# CH32V002F4U6.net
KiCad netlist of a schematic drawn in Altium Designer
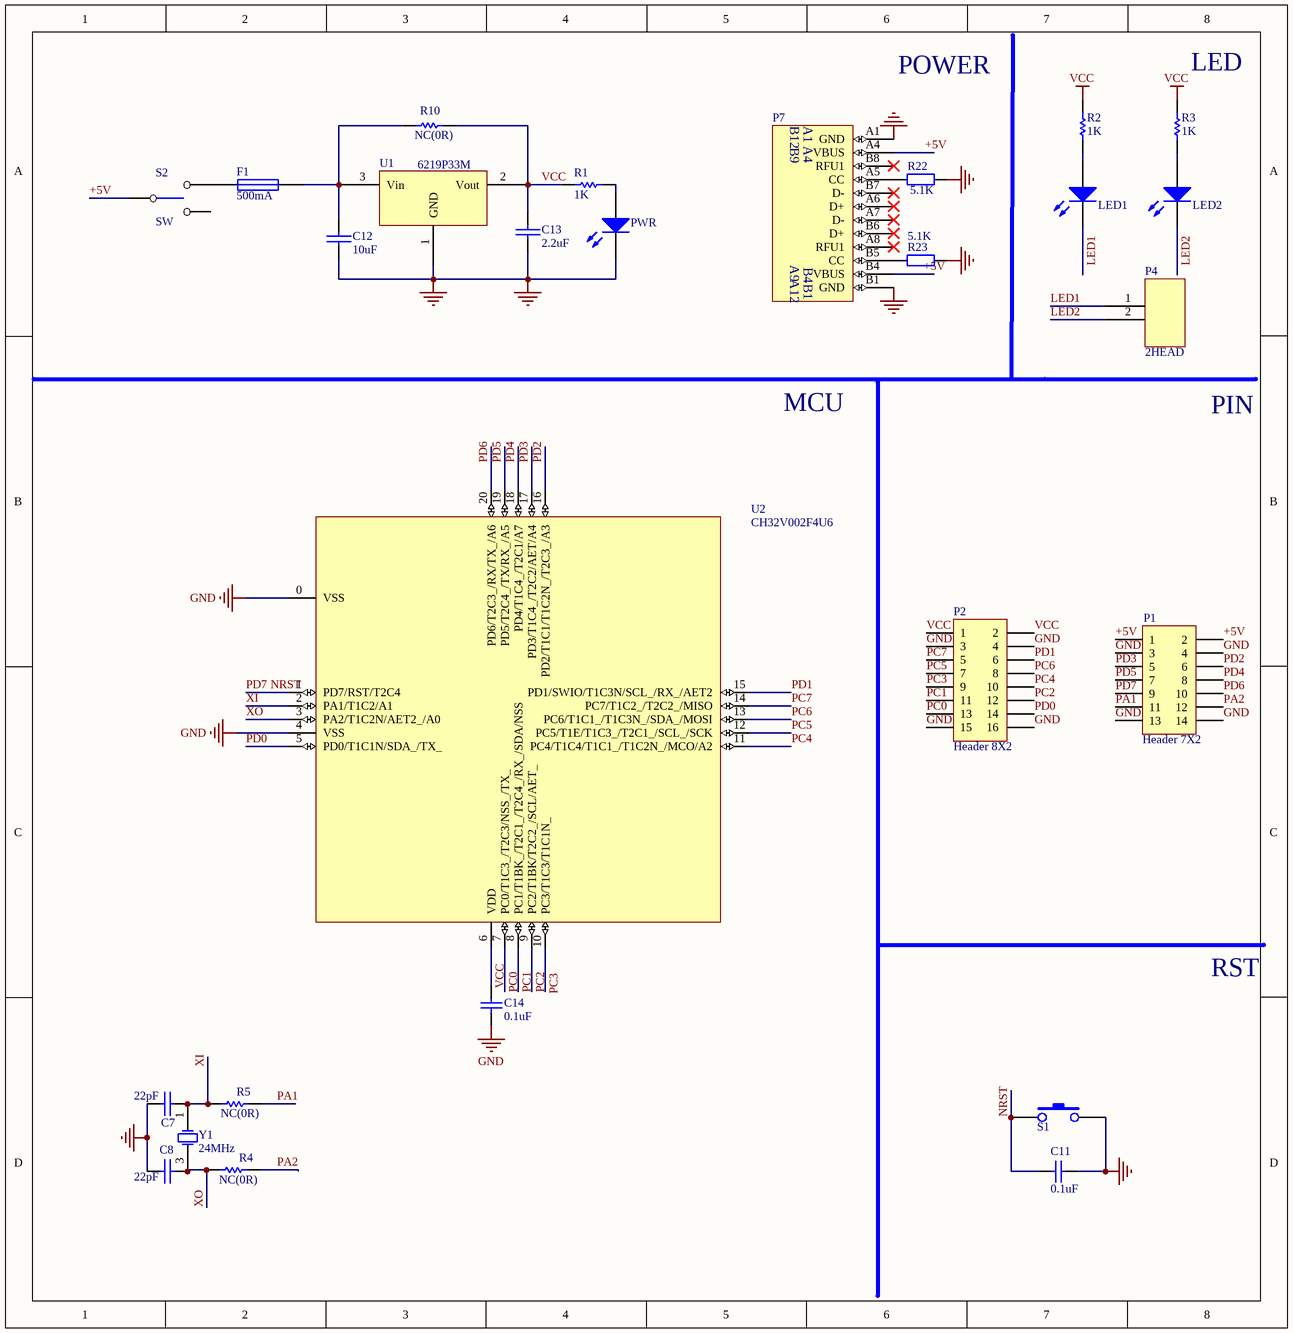
[diagram p0: CH32V002F4U6.SchDoc]

(export (version "E")
  (design (tool "Eeschema 10.0.6"))
  (components
    (comp (ref "C7")
      (value "22pF")
      (footprint "0402_C")
      (description "Capacitor")
      (libsource (lib "*") (part "CAP"))
    )
    (comp (ref "C8")
      (value "22pF")
      (footprint "0402_C")
      (description "Capacitor")
      (libsource (lib "*") (part "CAP"))
    )
    (comp (ref "C11")
      (value "0.1uF")
      (footprint "0402_C")
      (description "Capacitor")
      (fields (field (name "PUBLISHER") "Altium Limited"))
      (libsource (lib "*") (part "Cap"))
    )
    (comp (ref "C12")
      (value "10uF")
      (footprint "0603_C")
      (description "Capacitor")
      (libsource (lib "wch_sch_others") (part "CAP"))
    )
    (comp (ref "C13")
      (value "2.2uF")
      (footprint "0402_C")
      (description "Capacitor")
      (libsource (lib "wch_sch_others") (part "CAP"))
    )
    (comp (ref "C14")
      (value "0.1uF")
      (footprint "0603_C")
      (description "Capacitor")
      (fields (field (name "PUBLISHER") "Altium Limited"))
      (libsource (lib "*") (part "Cap"))
    )
    (comp (ref "F1")
      (value "500mA")
      (footprint "0603")
      (description "Fuse")
      (libsource (lib "*") (part "FUSE1"))
    )
    (comp (ref "LED1")
      (value "LED1   blue")
      (footprint "0603+")
      (description "Typical INFRARED GaAs LED")
      (fields (field (name "PUBLISHER") "Altium Limited"))
      (libsource (lib "") (part "LED0_1"))
    )
    (comp (ref "LED2")
      (value "LED2  blue")
      (footprint "0603+")
      (description "Typical INFRARED GaAs LED")
      (fields (field (name "PUBLISHER") "Altium Limited"))
      (libsource (lib "") (part "LED0_1"))
    )
    (comp (ref "P1")
      (value "Header 7X2")
      (footprint "HDR2X7")
      (description "Header, 7-Pin, Dual row")
      (fields (field (name "PUBLISHER") "Altium Limited"))
      (libsource (lib "Miscellaneous Connectors") (part "Header 7X2"))
    )
    (comp (ref "P2")
      (value "Header 8X2")
      (footprint "HDR2X8")
      (description "Header, 8-Pin, Dual row")
      (fields (field (name "PUBLISHER") "Altium Limited"))
      (libsource (lib "Miscellaneous Connectors") (part "Header 8X2"))
    )
    (comp (ref "P4") (value "2HEAD") (footprint "SIP2-2.54mm") (libsource (lib "*") (part "2HEAD")))
    (comp (ref "P7")
      (value "TYPE-C")
      (footprint "TYPE-C-Receptacle-2.0")
      (libsource (lib "*") (part "TYPE-C1"))
    )
    (comp (ref "PWR")
      (value "POWER  red")
      (footprint "0603+")
      (description "Typical INFRARED GaAs LED")
      (fields (field (name "PUBLISHER") "Altium Limited"))
      (libsource (lib "*") (part "LED0"))
    )
    (comp (ref "R1")
      (value "1K")
      (footprint "0402")
      (description "Semiconductor Resistor")
      (fields (field (name "PUBLISHER") "Altium Limited"))
      (libsource (lib "*") (part "Res Semi"))
    )
    (comp (ref "R2")
      (value "1K")
      (footprint "0402")
      (description "Semiconductor Resistor")
      (fields (field (name "PUBLISHER") "Altium Limited"))
      (libsource (lib "*") (part "Res Semi"))
    )
    (comp (ref "R3")
      (value "1K")
      (footprint "0402")
      (description "Semiconductor Resistor")
      (fields (field (name "PUBLISHER") "Altium Limited"))
      (libsource (lib "*") (part "Res Semi"))
    )
    (comp (ref "R4")
      (value "NC(0R)")
      (footprint "0402")
      (description "Semiconductor Resistor")
      (fields (field (name "Comment") "0R") (field (name "PUBLISHER") "Altium Limited"))
      (libsource (lib "*") (part "Res Semi"))
    )
    (comp (ref "R5")
      (value "NC(0R)")
      (footprint "0402")
      (description "Semiconductor Resistor")
      (fields (field (name "Comment") "0R") (field (name "PUBLISHER") "Altium Limited"))
      (libsource (lib "*") (part "Res Semi"))
    )
    (comp (ref "R10")
      (value "NC(0R)")
      (footprint "0402")
      (description "Semiconductor Resistor")
      (fields (field (name "Comment") "0R") (field (name "PUBLISHER") "Altium Limited"))
      (libsource (lib "*") (part "Res Semi"))
    )
    (comp (ref "R22")
      (value "5.1K")
      (footprint "0402")
      (description "Resistor")
      (libsource (lib "Miscellaneous Devices") (part "Res2"))
    )
    (comp (ref "R23")
      (value "5.1K")
      (footprint "0402")
      (description "Resistor")
      (libsource (lib "Miscellaneous Devices") (part "Res2"))
    )
    (comp (ref "S1") (value "NRST") (footprint "SMD_6.1x3.65x2.5mm-KEY") (libsource (lib "*") (part "KEY")))
    (comp (ref "S2") (value "SW") (footprint "SW1") (libsource (lib "*") (part "SW")))
    (comp (ref "U1")
      (value "6219P33M")
      (footprint "SOT-23")
      (libsource (lib "wch_sch_others") (part "6219P33M"))
    )
    (comp (ref "U2")
      (value "CH32V002F4U6")
      (footprint "QFN20_3X3")
      (description "RISC-V MCU, 48MHz, ADC/UART/I2C/SPI")
      (libsource (lib "DHXXXSCH") (part "CH32V002F4U6"))
    )
    (comp (ref "Y1")
      (value "24MHz")
      (footprint "XT3225")
      (description "Crystal Oscillator")
      (fields (field (name "PUBLISHER") "Altium Limited"))
      (libsource (lib "*") (part "XTAL"))
    )
  )
  (nets
    (net (code "1") (name "/+5V") (class "Default")
      (node (ref "P1") (pin "1") (pinfunction "1_1") (pintype "passive"))
      (node (ref "P1") (pin "2") (pinfunction "2_2") (pintype "passive"))
      (node (ref "P7") (pin "A4") (pinfunction "VBUS_A4") (pintype "bidirectional"))
      (node (ref "P7") (pin "B4") (pinfunction "VBUS_B4") (pintype "bidirectional"))
      (node (ref "S2") (pin "1") (pinfunction "1_1") (pintype "passive"))
    )
    (net (code "2") (name "/LED1") (class "Default")
      (node (ref "LED1") (pin "2") (pinfunction "K_2") (pintype "passive"))
      (node (ref "P4") (pin "1") (pintype "passive"))
    )
    (net (code "3") (name "/LED2") (class "Default")
      (node (ref "LED2") (pin "2") (pinfunction "K_2") (pintype "passive"))
      (node (ref "P4") (pin "2") (pintype "passive"))
    )
    (net (code "4") (name "/NRST") (class "Default")
      (node (ref "C11") (pin "2") (pinfunction "2_2") (pintype "passive"))
      (node (ref "P1") (pin "9") (pinfunction "9_9") (pintype "passive"))
      (node (ref "S1") (pin "1") (pinfunction "1_1") (pintype "passive"))
      (node (ref "U2") (pin "1") (pinfunction "PD7/RST/T2C4_1") (pintype "bidirectional"))
    )
    (net (code "5") (name "/PA1") (class "Default")
      (node (ref "P1") (pin "11") (pinfunction "11_11") (pintype "passive"))
      (node (ref "R5") (pin "2") (pinfunction "2_2") (pintype "passive"))
    )
    (net (code "6") (name "/PA2") (class "Default")
      (node (ref "P1") (pin "12") (pinfunction "12_12") (pintype "passive"))
      (node (ref "R4") (pin "2") (pinfunction "2_2") (pintype "passive"))
    )
    (net (code "7") (name "/PC0") (class "Default")
      (node (ref "P2") (pin "13") (pinfunction "13_13") (pintype "passive"))
      (node (ref "U2") (pin "7") (pinfunction "PC0/T1C3_/T2C3/NSS_/TX__7") (pintype "bidirectional"))
    )
    (net (code "8") (name "/PC1") (class "Default")
      (node (ref "P2") (pin "11") (pinfunction "11_11") (pintype "passive"))
      (node (ref "U2") (pin "8") (pinfunction "PC1/T1BK_/T2C1_/T2C4_/RX_/SDA/NSS_8") (pintype "bidirectional"))
    )
    (net (code "9") (name "/PC2") (class "Default")
      (node (ref "P2") (pin "12") (pinfunction "12_12") (pintype "passive"))
      (node (ref "U2") (pin "9") (pinfunction "PC2/T1BK/T2C2_/SCL/AET__9") (pintype "bidirectional"))
    )
    (net (code "10") (name "/PC3") (class "Default")
      (node (ref "P2") (pin "9") (pinfunction "9_9") (pintype "passive"))
      (node (ref "U2") (pin "10") (pinfunction "PC3/T1C3/T1C1N__10") (pintype "bidirectional"))
    )
    (net (code "11") (name "/PC4") (class "Default")
      (node (ref "P2") (pin "10") (pinfunction "10_10") (pintype "passive"))
      (node (ref "U2") (pin "11") (pinfunction "PC4/T1C4/T1C1_/T1C2N_/MCO/A2_11") (pintype "bidirectional"))
    )
    (net (code "12") (name "/PC5") (class "Default")
      (node (ref "P2") (pin "7") (pinfunction "7_7") (pintype "passive"))
      (node (ref "U2") (pin "12") (pinfunction "PC5/T1E/T1C3_/T2C1_/SCL_/SCK_12") (pintype "bidirectional"))
    )
    (net (code "13") (name "/PC6") (class "Default")
      (node (ref "P2") (pin "8") (pinfunction "8_8") (pintype "passive"))
      (node (ref "U2") (pin "13") (pinfunction "PC6/T1C1_/T1C3N_/SDA_/MOSI_13") (pintype "bidirectional"))
    )
    (net (code "14") (name "/PC7") (class "Default")
      (node (ref "P2") (pin "5") (pinfunction "5_5") (pintype "passive"))
      (node (ref "U2") (pin "14") (pinfunction "PC7/T1C2_/T2C2_/MISO_14") (pintype "bidirectional"))
    )
    (net (code "15") (name "/PD0") (class "Default")
      (node (ref "P2") (pin "14") (pinfunction "14_14") (pintype "passive"))
      (node (ref "U2") (pin "5") (pinfunction "PD0/T1C1N/SDA_/TX__5") (pintype "bidirectional"))
    )
    (net (code "16") (name "/PD1") (class "Default")
      (node (ref "P2") (pin "6") (pinfunction "6_6") (pintype "passive"))
      (node (ref "U2") (pin "15") (pinfunction "PD1/SWIO/T1C3N/SCL_/RX_/AET2_15") (pintype "bidirectional"))
    )
    (net (code "17") (name "/PD2") (class "Default")
      (node (ref "P1") (pin "6") (pinfunction "6_6") (pintype "passive"))
      (node (ref "U2") (pin "16") (pinfunction "PD2/T1C1/T1C2N_/T2C3_/A3_16") (pintype "bidirectional"))
    )
    (net (code "18") (name "/PD3") (class "Default")
      (node (ref "P1") (pin "5") (pinfunction "5_5") (pintype "passive"))
      (node (ref "U2") (pin "17") (pinfunction "PD3/T1C4_/T2C2/AET/A4_17") (pintype "bidirectional"))
    )
    (net (code "19") (name "/PD4") (class "Default")
      (node (ref "P1") (pin "8") (pinfunction "8_8") (pintype "passive"))
      (node (ref "U2") (pin "18") (pinfunction "PD4/T1C4_/T2C1/A7_18") (pintype "bidirectional"))
    )
    (net (code "20") (name "/PD5") (class "Default")
      (node (ref "P1") (pin "7") (pinfunction "7_7") (pintype "passive"))
      (node (ref "U2") (pin "19") (pinfunction "PD5/T2C4_/TX/RX_/A5_19") (pintype "bidirectional"))
    )
    (net (code "21") (name "/PD6") (class "Default")
      (node (ref "P1") (pin "10") (pinfunction "10_10") (pintype "passive"))
      (node (ref "U2") (pin "20") (pinfunction "PD6/T2C3_/RX/TX_/A6_20") (pintype "bidirectional"))
    )
    (net (code "22") (name "/XI") (class "Default")
      (node (ref "C7") (pin "2") (pinfunction "2_2") (pintype "passive"))
      (node (ref "R5") (pin "1") (pinfunction "1_1") (pintype "passive"))
      (node (ref "U2") (pin "2") (pinfunction "PA1/T1C2/A1_2") (pintype "bidirectional"))
      (node (ref "Y1") (pin "1") (pinfunction "OSC1_1") (pintype "passive"))
    )
    (net (code "23") (name "/XO") (class "Default")
      (node (ref "C8") (pin "2") (pinfunction "2_2") (pintype "passive"))
      (node (ref "R4") (pin "1") (pinfunction "1_1") (pintype "passive"))
      (node (ref "U2") (pin "3") (pinfunction "PA2/T1C2N/AET2_/A0_3") (pintype "bidirectional"))
      (node (ref "Y1") (pin "3") (pinfunction "OSC2_3") (pintype "passive"))
    )
    (net (code "24") (name "GND") (class "Default")
      (node (ref "C11") (pin "1") (pinfunction "1_1") (pintype "passive"))
      (node (ref "C12") (pin "2") (pinfunction "2_2") (pintype "passive"))
      (node (ref "C13") (pin "1") (pinfunction "1_1") (pintype "passive"))
      (node (ref "C14") (pin "2") (pinfunction "2_2") (pintype "passive"))
      (node (ref "C7") (pin "1") (pinfunction "1_1") (pintype "passive"))
      (node (ref "C8") (pin "1") (pinfunction "1_1") (pintype "passive"))
      (node (ref "P1") (pin "13") (pinfunction "13_13") (pintype "passive"))
      (node (ref "P1") (pin "14") (pinfunction "14_14") (pintype "passive"))
      (node (ref "P1") (pin "3") (pinfunction "3_3") (pintype "passive"))
      (node (ref "P1") (pin "4") (pinfunction "4_4") (pintype "passive"))
      (node (ref "P2") (pin "15") (pinfunction "15_15") (pintype "passive"))
      (node (ref "P2") (pin "16") (pinfunction "16_16") (pintype "passive"))
      (node (ref "P2") (pin "3") (pinfunction "3_3") (pintype "passive"))
      (node (ref "P2") (pin "4") (pinfunction "4_4") (pintype "passive"))
      (node (ref "P7") (pin "A1") (pinfunction "GND_A1") (pintype "bidirectional"))
      (node (ref "P7") (pin "B1") (pinfunction "GND_B1") (pintype "bidirectional"))
      (node (ref "PWR") (pin "2") (pinfunction "K_2") (pintype "passive"))
      (node (ref "R22") (pin "2") (pinfunction "2_2") (pintype "passive"))
      (node (ref "R23") (pin "2") (pinfunction "2_2") (pintype "passive"))
      (node (ref "S1") (pin "2") (pinfunction "2_2") (pintype "passive"))
      (node (ref "U1") (pin "1") (pinfunction "GND_1") (pintype "passive"))
      (node (ref "U2") (pin "0") (pinfunction "VSS_0") (pintype "power_in"))
      (node (ref "U2") (pin "4") (pinfunction "VSS_4") (pintype "power_in"))
    )
    (net (code "25") (name "Net-(F1-Pad1)") (class "Default")
      (node (ref "F1") (pin "1") (pinfunction "1_1") (pintype "passive"))
      (node (ref "S2") (pin "3") (pinfunction "3_3") (pintype "passive"))
    )
    (net (code "26") (name "Net-(LED1-A)") (class "Default")
      (node (ref "LED1") (pin "1") (pinfunction "A_1") (pintype "passive"))
      (node (ref "R2") (pin "2") (pinfunction "2_2") (pintype "passive"))
    )
    (net (code "27") (name "Net-(LED2-A)") (class "Default")
      (node (ref "LED2") (pin "1") (pinfunction "A_1") (pintype "passive"))
      (node (ref "R3") (pin "2") (pinfunction "2_2") (pintype "passive"))
    )
    (net (code "28") (name "Net-(P7-CC-PadA5)") (class "Default")
      (node (ref "P7") (pin "A5") (pinfunction "CC_A5") (pintype "bidirectional"))
      (node (ref "R22") (pin "1") (pinfunction "1_1") (pintype "passive"))
    )
    (net (code "29") (name "Net-(P7-CC-PadB5)") (class "Default")
      (node (ref "P7") (pin "B5") (pinfunction "CC_B5") (pintype "bidirectional"))
      (node (ref "R23") (pin "1") (pinfunction "1_1") (pintype "passive"))
    )
    (net (code "30") (name "Net-(PWR-A)") (class "Default")
      (node (ref "PWR") (pin "1") (pinfunction "A_1") (pintype "passive"))
      (node (ref "R1") (pin "1") (pinfunction "1_1") (pintype "passive"))
    )
    (net (code "31") (name "Net-(U1-Vin)") (class "Default")
      (node (ref "C12") (pin "1") (pinfunction "1_1") (pintype "passive"))
      (node (ref "F1") (pin "2") (pinfunction "2_2") (pintype "passive"))
      (node (ref "R10") (pin "1") (pinfunction "1_1") (pintype "passive"))
      (node (ref "U1") (pin "3") (pinfunction "Vin_3") (pintype "passive"))
    )
    (net (code "32") (name "VCC") (class "Default")
      (node (ref "C13") (pin "2") (pinfunction "2_2") (pintype "passive"))
      (node (ref "C14") (pin "1") (pinfunction "1_1") (pintype "passive"))
      (node (ref "P2") (pin "1") (pinfunction "1_1") (pintype "passive"))
      (node (ref "P2") (pin "2") (pinfunction "2_2") (pintype "passive"))
      (node (ref "R1") (pin "2") (pinfunction "2_2") (pintype "passive"))
      (node (ref "R10") (pin "2") (pinfunction "2_2") (pintype "passive"))
      (node (ref "R2") (pin "1") (pinfunction "1_1") (pintype "passive"))
      (node (ref "R3") (pin "1") (pinfunction "1_1") (pintype "passive"))
      (node (ref "U1") (pin "2") (pinfunction "Vout_2") (pintype "passive"))
      (node (ref "U2") (pin "6") (pinfunction "VDD_6") (pintype "power_in"))
    )
    (net (code "33") (name "unconnected-(P7-D+-PadA6)") (class "Default")
      (node (ref "P7") (pin "A6") (pinfunction "D+_A6") (pintype "bidirectional+no_connect"))
    )
    (net (code "34") (name "unconnected-(P7-D+-PadB6)") (class "Default")
      (node (ref "P7") (pin "B6") (pinfunction "D+_B6") (pintype "bidirectional+no_connect"))
    )
    (net (code "35") (name "unconnected-(P7-D--PadA7)") (class "Default")
      (node (ref "P7") (pin "A7") (pinfunction "D-_A7") (pintype "bidirectional+no_connect"))
    )
    (net (code "36") (name "unconnected-(P7-D--PadB7)") (class "Default")
      (node (ref "P7") (pin "B7") (pinfunction "D-_B7") (pintype "bidirectional+no_connect"))
    )
    (net (code "37") (name "unconnected-(P7-RFU1-PadA8)") (class "Default")
      (node (ref "P7") (pin "A8") (pinfunction "RFU1_A8") (pintype "bidirectional+no_connect"))
    )
    (net (code "38") (name "unconnected-(P7-RFU1-PadB8)") (class "Default")
      (node (ref "P7") (pin "B8") (pinfunction "RFU1_B8") (pintype "bidirectional+no_connect"))
    )
    (net (code "39") (name "unconnected-(S2-Pad2)") (class "Default")
      (node (ref "S2") (pin "2") (pinfunction "2_2") (pintype "passive"))
    )
  )
)
